# G851X.net
KiCad netlist of a schematic drawn in EAGLE
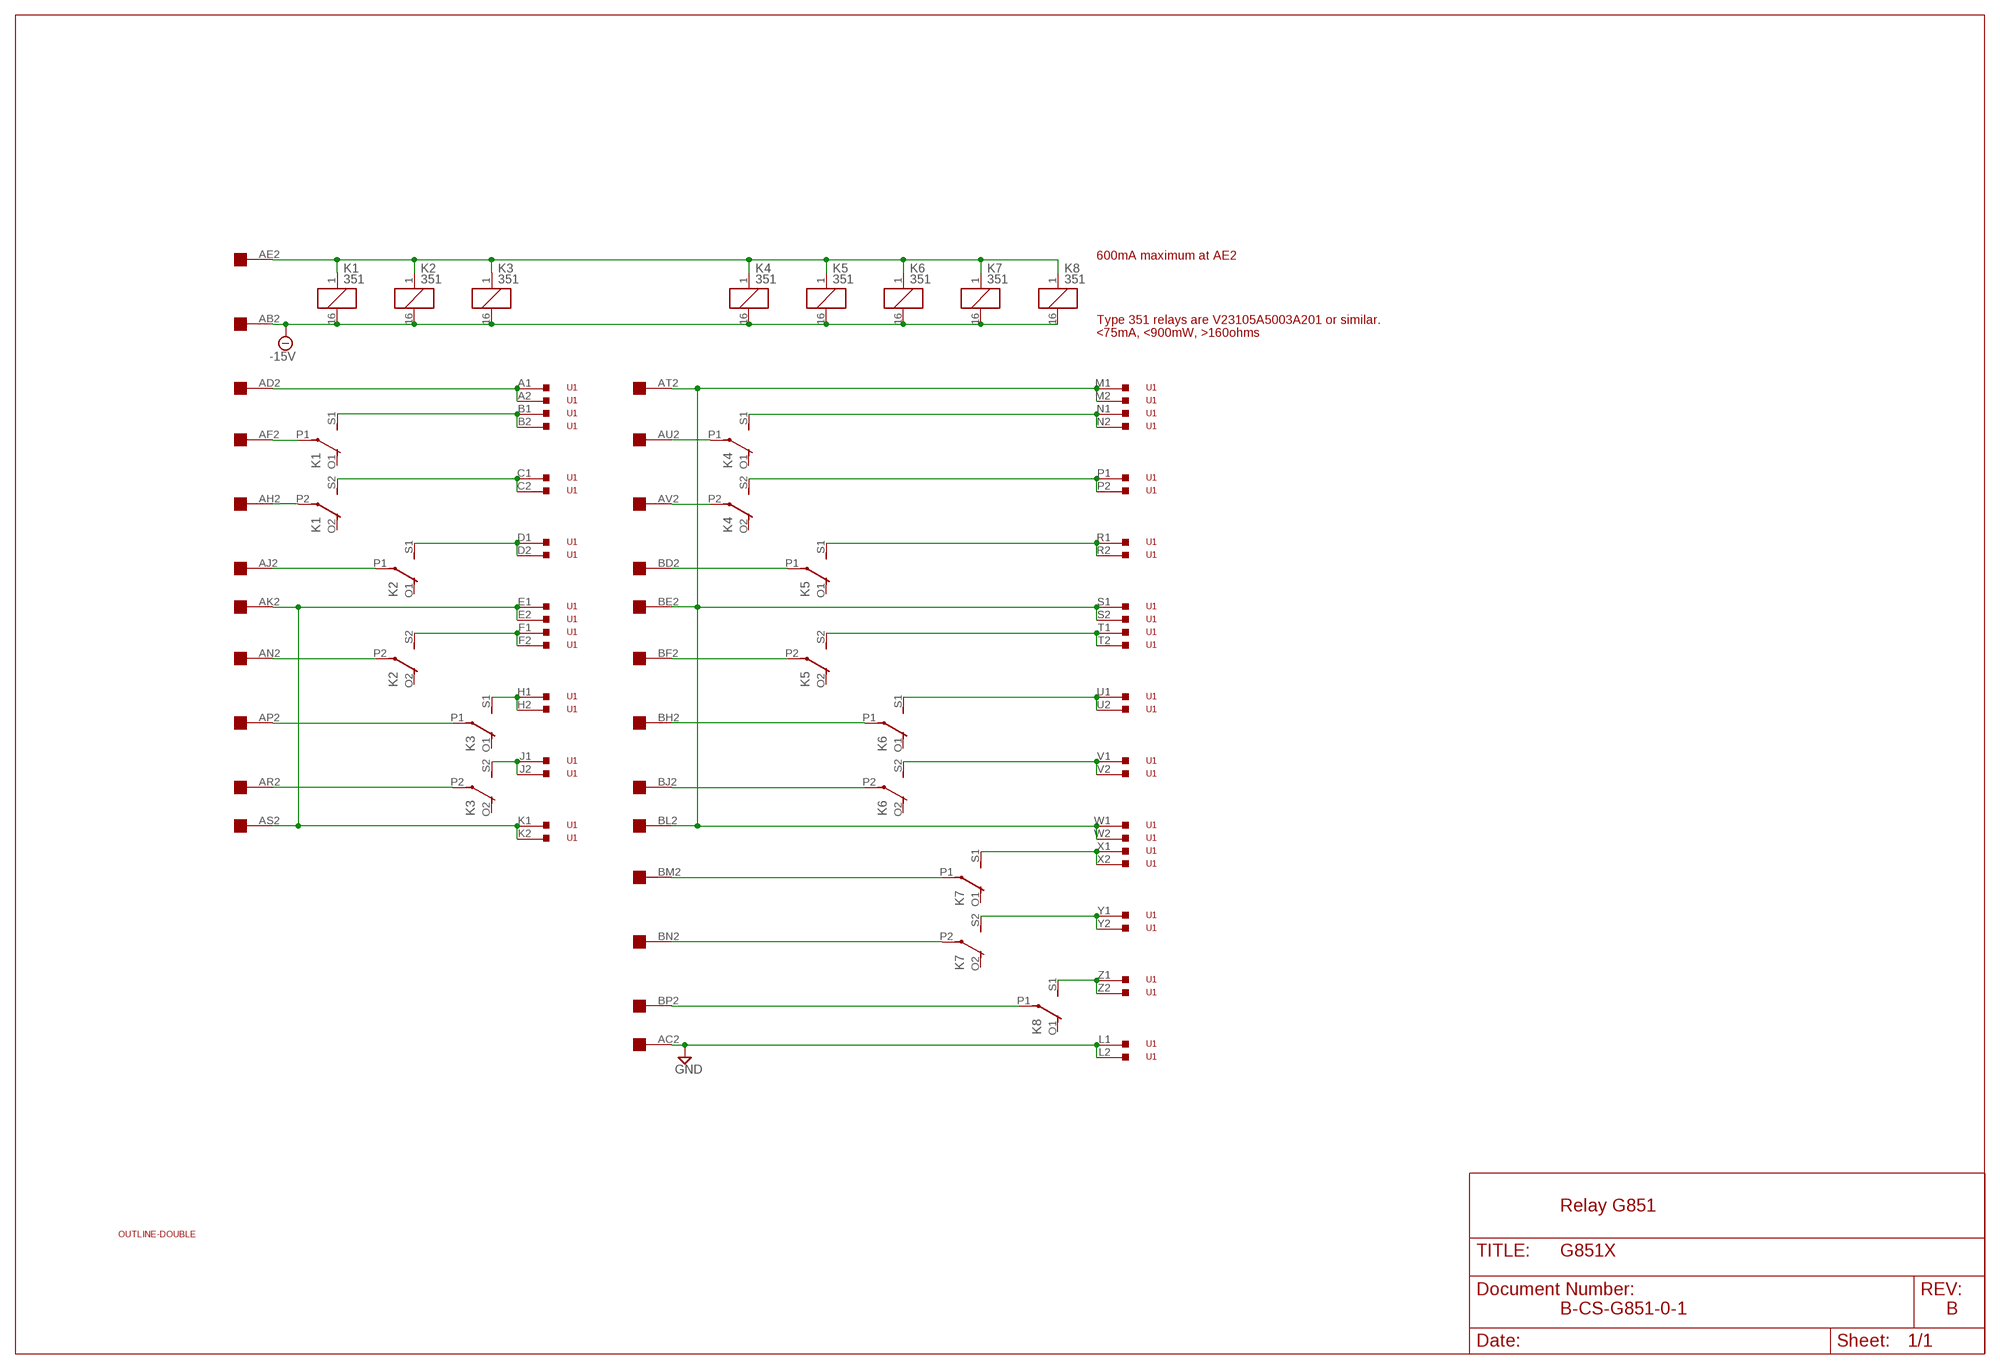
[diagram p0: schematic, sheet 1]

(export (version "E")
  (design (tool "Eeschema 10.0.6"))
  (components
    (comp (ref "K1")
      (value "351")
      (footprint "eagle-import:351")
      (libsource (lib "eagle-import") (part "351"))
    )
    (comp (ref "K2")
      (value "351")
      (footprint "eagle-import:351")
      (libsource (lib "eagle-import") (part "351"))
    )
    (comp (ref "K3")
      (value "351")
      (footprint "eagle-import:351")
      (libsource (lib "eagle-import") (part "351"))
    )
    (comp (ref "K4")
      (value "351")
      (footprint "eagle-import:351")
      (libsource (lib "eagle-import") (part "351"))
    )
    (comp (ref "K5")
      (value "351")
      (footprint "eagle-import:351")
      (libsource (lib "eagle-import") (part "351"))
    )
    (comp (ref "K6")
      (value "351")
      (footprint "eagle-import:351")
      (libsource (lib "eagle-import") (part "351"))
    )
    (comp (ref "K7")
      (value "351")
      (footprint "eagle-import:351")
      (libsource (lib "eagle-import") (part "351"))
    )
    (comp (ref "K8")
      (value "351")
      (footprint "eagle-import:351")
      (libsource (lib "eagle-import") (part "351"))
    )
    (comp (ref "U$1")
      (value "DOUBLE")
      (footprint "eagle-import:EDGE-CON4")
      (libsource (lib "eagle-import") (part "DOUBLE"))
    )
    (comp (ref "U$3")
      (value "OUTLINE-DOUBLE")
      (footprint "eagle-import:DOUBLE")
      (libsource (lib "eagle-import") (part "OUTLINE-DOUBLE"))
    )
    (comp (ref "U1")
      (value "S7346-ND")
      (footprint "eagle-import:133-022-03")
      (libsource (lib "eagle-import") (part "133-022-03"))
    )
  )
  (nets
    (net (code "1") (name "-15V") (class "Default")
      (node (ref "K1") (pin "16") (pinfunction "2_16") (pintype "passive"))
      (node (ref "K2") (pin "16") (pinfunction "2_16") (pintype "passive"))
      (node (ref "K3") (pin "16") (pinfunction "2_16") (pintype "passive"))
      (node (ref "K4") (pin "16") (pinfunction "2_16") (pintype "passive"))
      (node (ref "K5") (pin "16") (pinfunction "2_16") (pintype "passive"))
      (node (ref "K6") (pin "16") (pinfunction "2_16") (pintype "passive"))
      (node (ref "K7") (pin "16") (pinfunction "2_16") (pintype "passive"))
      (node (ref "K8") (pin "16") (pinfunction "2_16") (pintype "passive"))
      (node (ref "U$1") (pin "AB2") (pinfunction "1_AB2") (pintype "bidirectional"))
    )
    (net (code "2") (name "GND") (class "Default")
      (node (ref "U$1") (pin "AC2") (pinfunction "1_AC2") (pintype "bidirectional"))
      (node (ref "U1") (pin "L1") (pinfunction "P$2_L1") (pintype "bidirectional"))
      (node (ref "U1") (pin "L2") (pinfunction "P$2_L2") (pintype "bidirectional"))
    )
    (net (code "3") (name "Net-(K1B-P)") (class "Default")
      (node (ref "K1") (pin "P1") (pinfunction "P_P1") (pintype "passive"))
      (node (ref "U$1") (pin "AF2") (pinfunction "1_AF2") (pintype "bidirectional"))
    )
    (net (code "4") (name "Net-(K1B-S)") (class "Default")
      (node (ref "K1") (pin "S1") (pinfunction "S_S1") (pintype "passive"))
      (node (ref "U1") (pin "B1") (pinfunction "P$2_B1") (pintype "bidirectional"))
      (node (ref "U1") (pin "B2") (pinfunction "P$2_B2") (pintype "bidirectional"))
    )
    (net (code "5") (name "Net-(K1C-P)") (class "Default")
      (node (ref "K1") (pin "P2") (pinfunction "P_P2") (pintype "passive"))
      (node (ref "U$1") (pin "AH2") (pinfunction "1_AH2") (pintype "bidirectional"))
    )
    (net (code "6") (name "Net-(K1C-S)") (class "Default")
      (node (ref "K1") (pin "S2") (pinfunction "S_S2") (pintype "passive"))
      (node (ref "U1") (pin "C1") (pinfunction "P$2_C1") (pintype "bidirectional"))
      (node (ref "U1") (pin "C2") (pinfunction "P$2_C2") (pintype "bidirectional"))
    )
    (net (code "7") (name "Net-(K2B-P)") (class "Default")
      (node (ref "K2") (pin "P1") (pinfunction "P_P1") (pintype "passive"))
      (node (ref "U$1") (pin "AJ2") (pinfunction "1_AJ2") (pintype "bidirectional"))
    )
    (net (code "8") (name "Net-(K2B-S)") (class "Default")
      (node (ref "K2") (pin "S1") (pinfunction "S_S1") (pintype "passive"))
      (node (ref "U1") (pin "D1") (pinfunction "P$2_D1") (pintype "bidirectional"))
      (node (ref "U1") (pin "D2") (pinfunction "P$2_D2") (pintype "bidirectional"))
    )
    (net (code "9") (name "Net-(K2C-P)") (class "Default")
      (node (ref "K2") (pin "P2") (pinfunction "P_P2") (pintype "passive"))
      (node (ref "U$1") (pin "AN2") (pinfunction "1_AN2") (pintype "bidirectional"))
    )
    (net (code "10") (name "Net-(K2C-S)") (class "Default")
      (node (ref "K2") (pin "S2") (pinfunction "S_S2") (pintype "passive"))
      (node (ref "U1") (pin "F1") (pinfunction "P$2_F1") (pintype "bidirectional"))
      (node (ref "U1") (pin "F2") (pinfunction "P$2_F2") (pintype "bidirectional"))
    )
    (net (code "11") (name "Net-(K3B-P)") (class "Default")
      (node (ref "K3") (pin "P1") (pinfunction "P_P1") (pintype "passive"))
      (node (ref "U$1") (pin "AP2") (pinfunction "1_AP2") (pintype "bidirectional"))
    )
    (net (code "12") (name "Net-(K3B-S)") (class "Default")
      (node (ref "K3") (pin "S1") (pinfunction "S_S1") (pintype "passive"))
      (node (ref "U1") (pin "H1") (pinfunction "P$2_H1") (pintype "bidirectional"))
      (node (ref "U1") (pin "H2") (pinfunction "P$2_H2") (pintype "bidirectional"))
    )
    (net (code "13") (name "Net-(K3C-P)") (class "Default")
      (node (ref "K3") (pin "P2") (pinfunction "P_P2") (pintype "passive"))
      (node (ref "U$1") (pin "AR2") (pinfunction "1_AR2") (pintype "bidirectional"))
    )
    (net (code "14") (name "Net-(K3C-S)") (class "Default")
      (node (ref "K3") (pin "S2") (pinfunction "S_S2") (pintype "passive"))
      (node (ref "U1") (pin "J1") (pinfunction "P$2_J1") (pintype "bidirectional"))
      (node (ref "U1") (pin "J2") (pinfunction "P$2_J2") (pintype "bidirectional"))
    )
    (net (code "15") (name "Net-(K4B-P)") (class "Default")
      (node (ref "K4") (pin "P1") (pinfunction "P_P1") (pintype "passive"))
      (node (ref "U$1") (pin "AU2") (pinfunction "1_AU2") (pintype "bidirectional"))
    )
    (net (code "16") (name "Net-(K4B-S)") (class "Default")
      (node (ref "K4") (pin "S1") (pinfunction "S_S1") (pintype "passive"))
      (node (ref "U1") (pin "N1") (pinfunction "P$2_N1") (pintype "bidirectional"))
      (node (ref "U1") (pin "N2") (pinfunction "P$2_N2") (pintype "bidirectional"))
    )
    (net (code "17") (name "Net-(K4C-P)") (class "Default")
      (node (ref "K4") (pin "P2") (pinfunction "P_P2") (pintype "passive"))
      (node (ref "U$1") (pin "AV2") (pinfunction "1_AV2") (pintype "bidirectional"))
    )
    (net (code "18") (name "Net-(K4C-S)") (class "Default")
      (node (ref "K4") (pin "S2") (pinfunction "S_S2") (pintype "passive"))
      (node (ref "U1") (pin "P1") (pinfunction "P$2_P1") (pintype "bidirectional"))
      (node (ref "U1") (pin "P2") (pinfunction "P$2_P2") (pintype "bidirectional"))
    )
    (net (code "19") (name "Net-(K5B-P)") (class "Default")
      (node (ref "K5") (pin "P1") (pinfunction "P_P1") (pintype "passive"))
      (node (ref "U$1") (pin "BD2") (pinfunction "1_BD2") (pintype "bidirectional"))
    )
    (net (code "20") (name "Net-(K5B-S)") (class "Default")
      (node (ref "K5") (pin "S1") (pinfunction "S_S1") (pintype "passive"))
      (node (ref "U1") (pin "R1") (pinfunction "P$2_R1") (pintype "bidirectional"))
      (node (ref "U1") (pin "R2") (pinfunction "P$2_R2") (pintype "bidirectional"))
    )
    (net (code "21") (name "Net-(K5C-P)") (class "Default")
      (node (ref "K5") (pin "P2") (pinfunction "P_P2") (pintype "passive"))
      (node (ref "U$1") (pin "BF2") (pinfunction "1_BF2") (pintype "bidirectional"))
    )
    (net (code "22") (name "Net-(K5C-S)") (class "Default")
      (node (ref "K5") (pin "S2") (pinfunction "S_S2") (pintype "passive"))
      (node (ref "U1") (pin "T1") (pinfunction "P$2_T1") (pintype "bidirectional"))
      (node (ref "U1") (pin "T2") (pinfunction "P$2_T2") (pintype "bidirectional"))
    )
    (net (code "23") (name "Net-(K6B-P)") (class "Default")
      (node (ref "K6") (pin "P1") (pinfunction "P_P1") (pintype "passive"))
      (node (ref "U$1") (pin "BH2") (pinfunction "1_BH2") (pintype "bidirectional"))
    )
    (net (code "24") (name "Net-(K6B-S)") (class "Default")
      (node (ref "K6") (pin "S1") (pinfunction "S_S1") (pintype "passive"))
      (node (ref "U1") (pin "U1") (pinfunction "P$2_U1") (pintype "bidirectional"))
      (node (ref "U1") (pin "U2") (pinfunction "P$2_U2") (pintype "bidirectional"))
    )
    (net (code "25") (name "Net-(K6C-P)") (class "Default")
      (node (ref "K6") (pin "P2") (pinfunction "P_P2") (pintype "passive"))
      (node (ref "U$1") (pin "BJ2") (pinfunction "1_BJ2") (pintype "bidirectional"))
    )
    (net (code "26") (name "Net-(K6C-S)") (class "Default")
      (node (ref "K6") (pin "S2") (pinfunction "S_S2") (pintype "passive"))
      (node (ref "U1") (pin "V1") (pinfunction "P$2_V1") (pintype "bidirectional"))
      (node (ref "U1") (pin "V2") (pinfunction "P$2_V2") (pintype "bidirectional"))
    )
    (net (code "27") (name "Net-(K7B-P)") (class "Default")
      (node (ref "K7") (pin "P1") (pinfunction "P_P1") (pintype "passive"))
      (node (ref "U$1") (pin "BM2") (pinfunction "1_BM2") (pintype "bidirectional"))
    )
    (net (code "28") (name "Net-(K7B-S)") (class "Default")
      (node (ref "K7") (pin "S1") (pinfunction "S_S1") (pintype "passive"))
      (node (ref "U1") (pin "X1") (pinfunction "P$2_X1") (pintype "bidirectional"))
      (node (ref "U1") (pin "X2") (pinfunction "P$2_X2") (pintype "bidirectional"))
    )
    (net (code "29") (name "Net-(K7C-P)") (class "Default")
      (node (ref "K7") (pin "P2") (pinfunction "P_P2") (pintype "passive"))
      (node (ref "U$1") (pin "BN2") (pinfunction "1_BN2") (pintype "bidirectional"))
    )
    (net (code "30") (name "Net-(K7C-S)") (class "Default")
      (node (ref "K7") (pin "S2") (pinfunction "S_S2") (pintype "passive"))
      (node (ref "U1") (pin "Y1") (pinfunction "P$2_Y1") (pintype "bidirectional"))
      (node (ref "U1") (pin "Y2") (pinfunction "P$2_Y2") (pintype "bidirectional"))
    )
    (net (code "31") (name "Net-(K8B-P)") (class "Default")
      (node (ref "K8") (pin "P1") (pinfunction "P_P1") (pintype "passive"))
      (node (ref "U$1") (pin "BP2") (pinfunction "1_BP2") (pintype "bidirectional"))
    )
    (net (code "32") (name "Net-(K8B-S)") (class "Default")
      (node (ref "K8") (pin "S1") (pinfunction "S_S1") (pintype "passive"))
      (node (ref "U1") (pin "Z1") (pinfunction "P$2_Z1") (pintype "bidirectional"))
      (node (ref "U1") (pin "Z2") (pinfunction "P$2_Z2") (pintype "bidirectional"))
    )
    (net (code "33") (name "Net-(U$1AD-1)") (class "Default")
      (node (ref "U$1") (pin "AK2") (pinfunction "1_AK2") (pintype "bidirectional"))
      (node (ref "U$1") (pin "AS2") (pinfunction "1_AS2") (pintype "bidirectional"))
      (node (ref "U1") (pin "E1") (pinfunction "P$2_E1") (pintype "bidirectional"))
      (node (ref "U1") (pin "E2") (pinfunction "P$2_E2") (pintype "bidirectional"))
      (node (ref "U1") (pin "K1") (pinfunction "P$2_K1") (pintype "bidirectional"))
      (node (ref "U1") (pin "K2") (pinfunction "P$2_K2") (pintype "bidirectional"))
    )
    (net (code "34") (name "Net-(U$1AF-1)") (class "Default")
      (node (ref "U$1") (pin "AT2") (pinfunction "1_AT2") (pintype "bidirectional"))
      (node (ref "U$1") (pin "BE2") (pinfunction "1_BE2") (pintype "bidirectional"))
      (node (ref "U$1") (pin "BL2") (pinfunction "1_BL2") (pintype "bidirectional"))
      (node (ref "U1") (pin "M1") (pinfunction "P$2_M1") (pintype "bidirectional"))
      (node (ref "U1") (pin "M2") (pinfunction "P$2_M2") (pintype "bidirectional"))
      (node (ref "U1") (pin "S1") (pinfunction "P$2_S1") (pintype "bidirectional"))
      (node (ref "U1") (pin "S2") (pinfunction "P$2_S2") (pintype "bidirectional"))
      (node (ref "U1") (pin "W1") (pinfunction "P$2_W1") (pintype "bidirectional"))
      (node (ref "U1") (pin "W2") (pinfunction "P$2_W2") (pintype "bidirectional"))
    )
    (net (code "35") (name "Net-(U$1H-1)") (class "Default")
      (node (ref "U$1") (pin "AD2") (pinfunction "1_AD2") (pintype "bidirectional"))
      (node (ref "U1") (pin "A1") (pinfunction "P$2_A1") (pintype "bidirectional"))
      (node (ref "U1") (pin "A2") (pinfunction "P$2_A2") (pintype "bidirectional"))
    )
    (net (code "36") (name "Net-(U$1J-1)") (class "Default")
      (node (ref "K1") (pin "1") (pinfunction "1_1") (pintype "passive"))
      (node (ref "K2") (pin "1") (pinfunction "1_1") (pintype "passive"))
      (node (ref "K3") (pin "1") (pinfunction "1_1") (pintype "passive"))
      (node (ref "K4") (pin "1") (pinfunction "1_1") (pintype "passive"))
      (node (ref "K5") (pin "1") (pinfunction "1_1") (pintype "passive"))
      (node (ref "K6") (pin "1") (pinfunction "1_1") (pintype "passive"))
      (node (ref "K7") (pin "1") (pinfunction "1_1") (pintype "passive"))
      (node (ref "K8") (pin "1") (pinfunction "1_1") (pintype "passive"))
      (node (ref "U$1") (pin "AE2") (pinfunction "1_AE2") (pintype "bidirectional"))
    )
    (net (code "37") (name "unconnected-(K1B-O-PadO1)") (class "Default")
      (node (ref "K1") (pin "O1") (pinfunction "O_O1") (pintype "passive"))
    )
    (net (code "38") (name "unconnected-(K1C-O-PadO2)") (class "Default")
      (node (ref "K1") (pin "O2") (pinfunction "O_O2") (pintype "passive"))
    )
    (net (code "39") (name "unconnected-(K2B-O-PadO1)") (class "Default")
      (node (ref "K2") (pin "O1") (pinfunction "O_O1") (pintype "passive"))
    )
    (net (code "40") (name "unconnected-(K2C-O-PadO2)") (class "Default")
      (node (ref "K2") (pin "O2") (pinfunction "O_O2") (pintype "passive"))
    )
    (net (code "41") (name "unconnected-(K3B-O-PadO1)") (class "Default")
      (node (ref "K3") (pin "O1") (pinfunction "O_O1") (pintype "passive"))
    )
    (net (code "42") (name "unconnected-(K3C-O-PadO2)") (class "Default")
      (node (ref "K3") (pin "O2") (pinfunction "O_O2") (pintype "passive"))
    )
    (net (code "43") (name "unconnected-(K4B-O-PadO1)") (class "Default")
      (node (ref "K4") (pin "O1") (pinfunction "O_O1") (pintype "passive"))
    )
    (net (code "44") (name "unconnected-(K4C-O-PadO2)") (class "Default")
      (node (ref "K4") (pin "O2") (pinfunction "O_O2") (pintype "passive"))
    )
    (net (code "45") (name "unconnected-(K5B-O-PadO1)") (class "Default")
      (node (ref "K5") (pin "O1") (pinfunction "O_O1") (pintype "passive"))
    )
    (net (code "46") (name "unconnected-(K5C-O-PadO2)") (class "Default")
      (node (ref "K5") (pin "O2") (pinfunction "O_O2") (pintype "passive"))
    )
    (net (code "47") (name "unconnected-(K6B-O-PadO1)") (class "Default")
      (node (ref "K6") (pin "O1") (pinfunction "O_O1") (pintype "passive"))
    )
    (net (code "48") (name "unconnected-(K6C-O-PadO2)") (class "Default")
      (node (ref "K6") (pin "O2") (pinfunction "O_O2") (pintype "passive"))
    )
    (net (code "49") (name "unconnected-(K7B-O-PadO1)") (class "Default")
      (node (ref "K7") (pin "O1") (pinfunction "O_O1") (pintype "passive"))
    )
    (net (code "50") (name "unconnected-(K7C-O-PadO2)") (class "Default")
      (node (ref "K7") (pin "O2") (pinfunction "O_O2") (pintype "passive"))
    )
    (net (code "51") (name "unconnected-(K8B-O-PadO1)") (class "Default")
      (node (ref "K8") (pin "O1") (pinfunction "O_O1") (pintype "passive"))
    )
  )
)
